# M4_Shield_Solar_Litio_V1_0.net
KiCad netlist of a schematic drawn in EAGLE
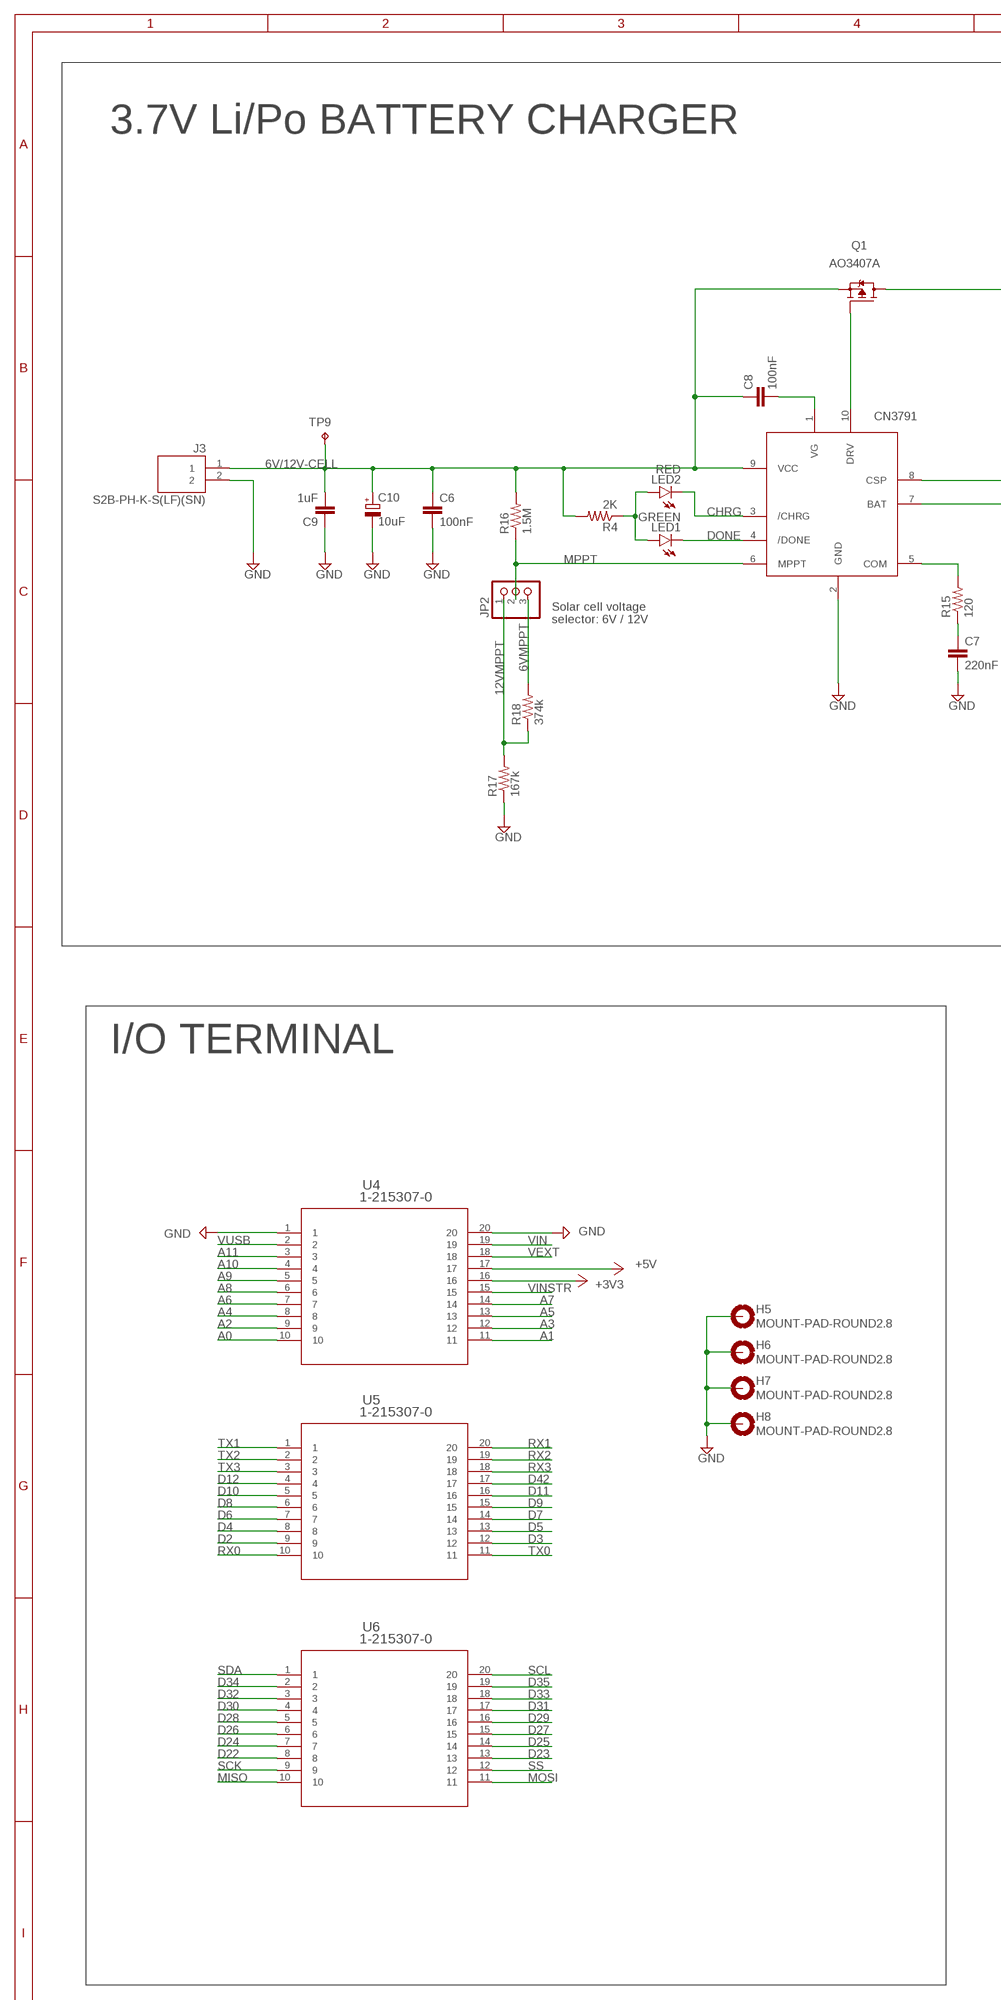
[diagram p0: schematic, sheet 1, part 1 of 2]
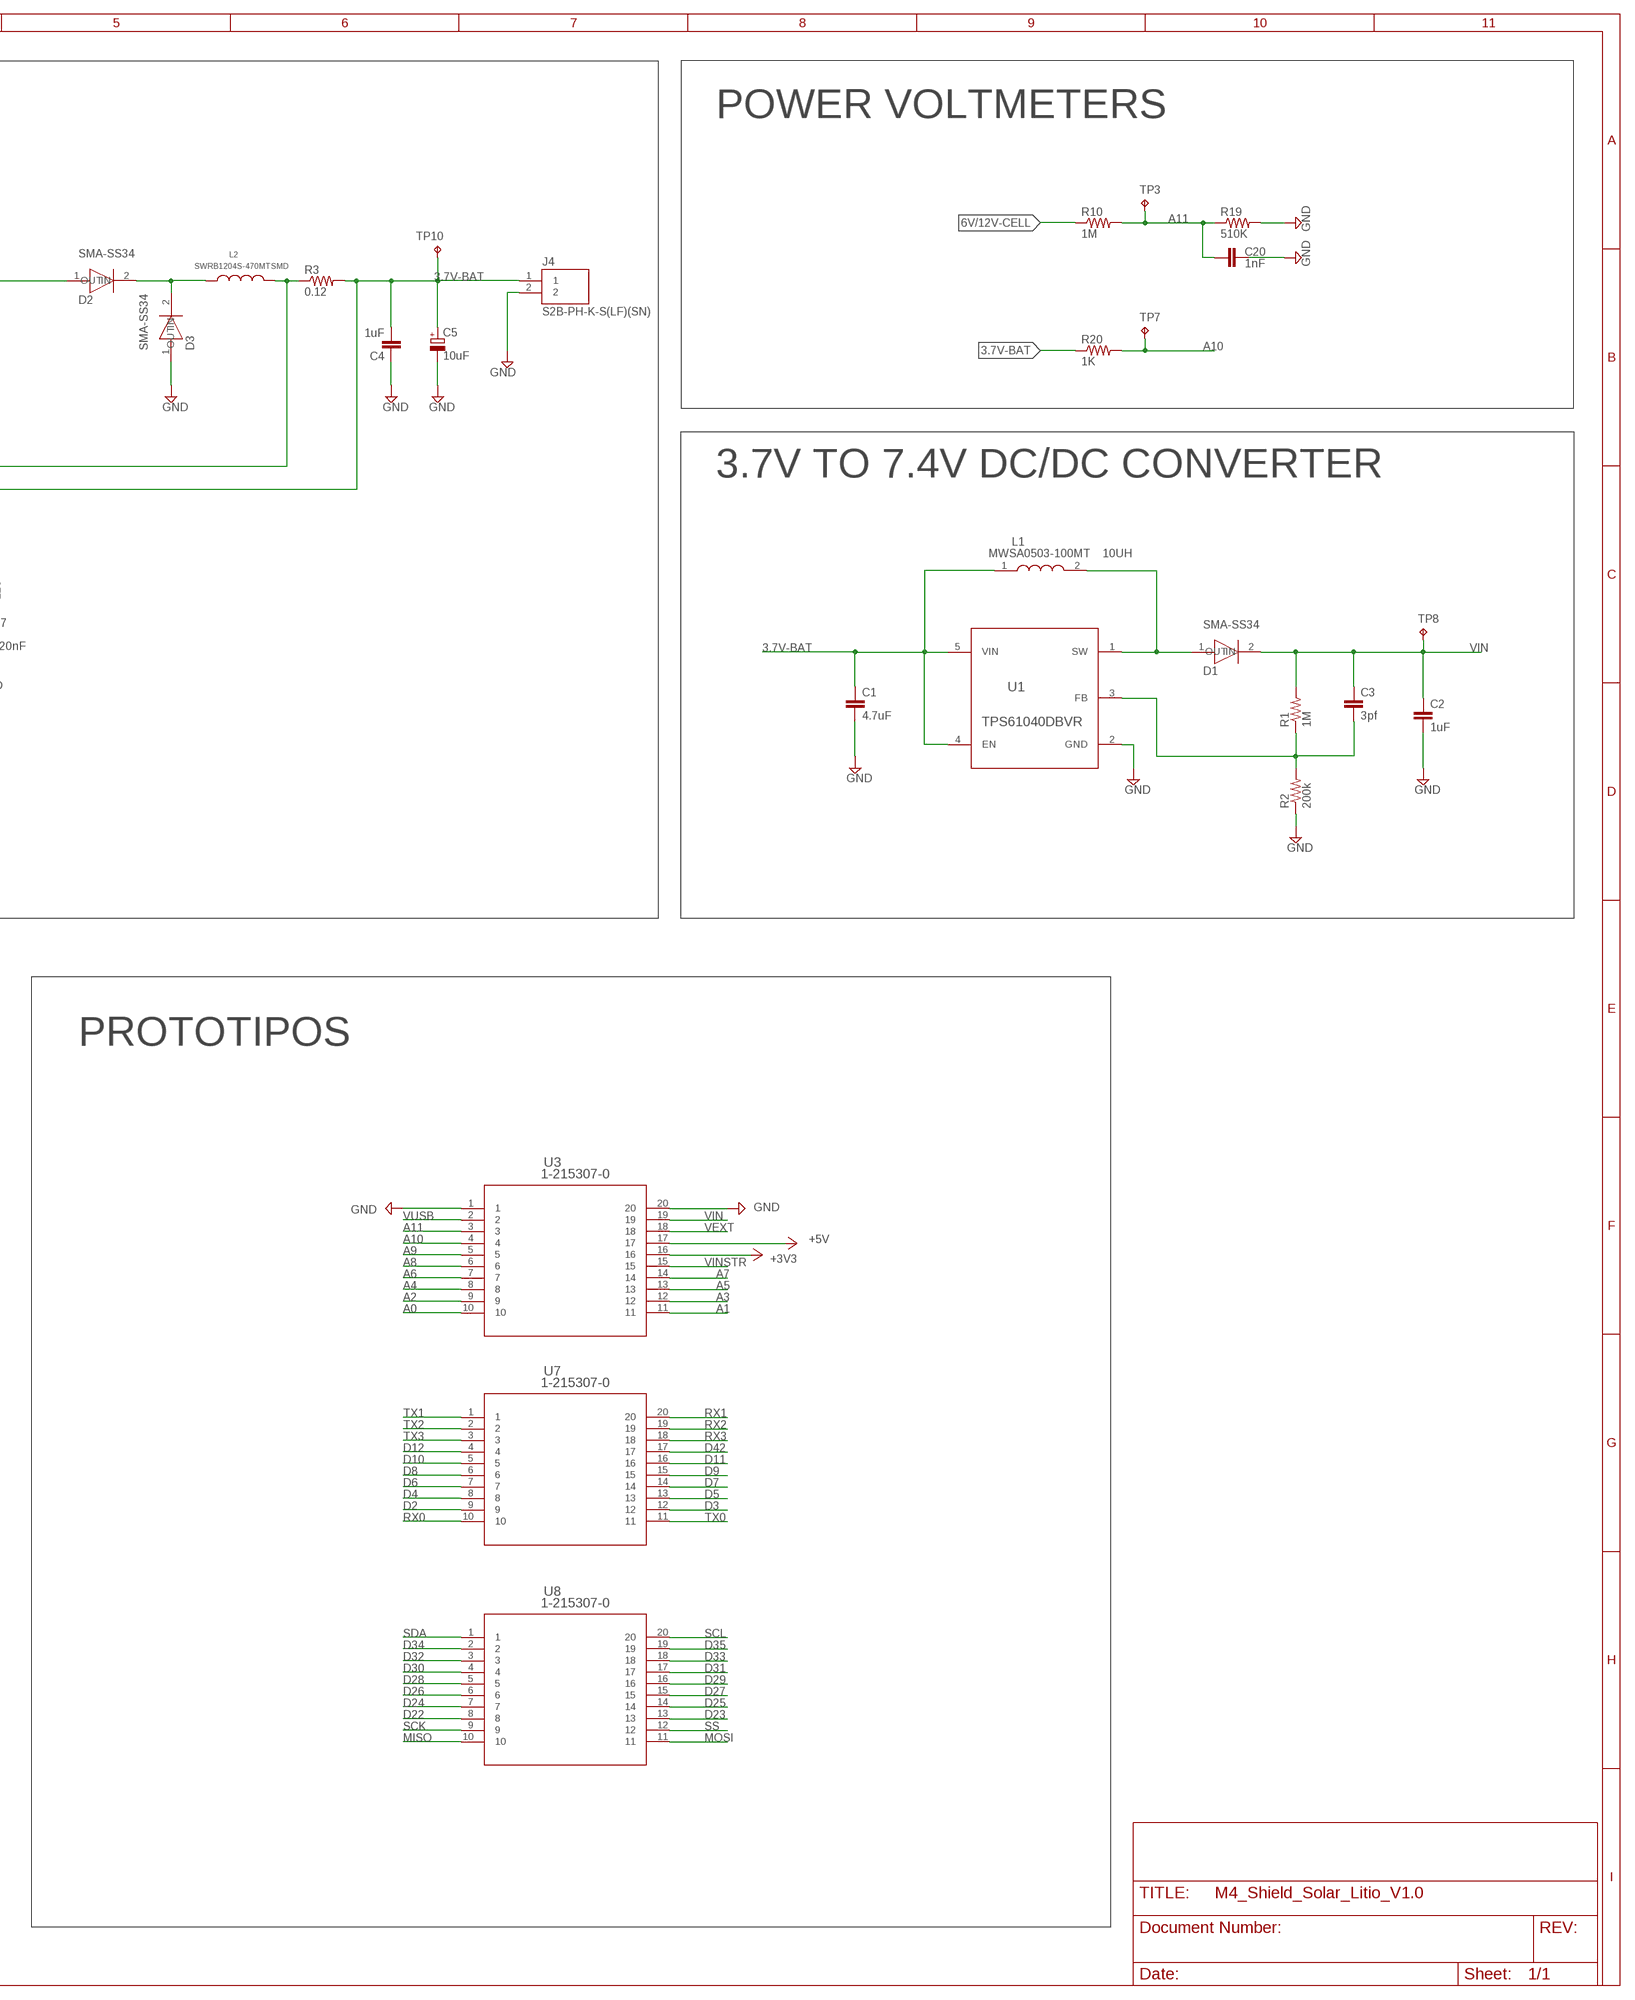
[diagram p1: schematic, sheet 1, part 2 of 2]

(export (version "E")
  (design (tool "Eeschema 10.0.6"))
  (components
    (comp (ref "C1")
      (value "4.7uF")
      (footprint "eagle-import:C0603K")
      (libsource (lib "eagle-import") (part "C-EUC0603K"))
    )
    (comp (ref "C2")
      (value "1uF")
      (footprint "eagle-import:C0603K")
      (libsource (lib "eagle-import") (part "C-EUC0603K"))
    )
    (comp (ref "C3")
      (value "3pf")
      (footprint "eagle-import:C0603K")
      (libsource (lib "eagle-import") (part "C-EUC0603K"))
    )
    (comp (ref "C4")
      (value "1uF")
      (footprint "eagle-import:C0603K")
      (libsource (lib "eagle-import") (part "C-EUC0603K"))
    )
    (comp (ref "C5")
      (value "10uF")
      (footprint "eagle-import:153CLV-0505")
      (libsource (lib "eagle-import") (part "CPOL-EU153CLV-0505"))
    )
    (comp (ref "C6")
      (value "100nF")
      (footprint "eagle-import:C0603K")
      (libsource (lib "eagle-import") (part "C-EUC0603K"))
    )
    (comp (ref "C7")
      (value "220nF")
      (footprint "eagle-import:C0603K")
      (libsource (lib "eagle-import") (part "C-EUC0603K"))
    )
    (comp (ref "C8")
      (value "100nF")
      (footprint "eagle-import:C0603K")
      (libsource (lib "eagle-import") (part "C-EUC0603K"))
    )
    (comp (ref "C9")
      (value "1uF")
      (footprint "eagle-import:C0603K")
      (libsource (lib "eagle-import") (part "C-EUC0603K"))
    )
    (comp (ref "C10")
      (value "10uF")
      (footprint "eagle-import:153CLV-0505")
      (libsource (lib "eagle-import") (part "CPOL-EU153CLV-0505"))
    )
    (comp (ref "C20")
      (value "1nF")
      (footprint "eagle-import:C0603K")
      (libsource (lib "eagle-import") (part "C-EUC0603K"))
    )
    (comp (ref "D1")
      (value "SMA-SS34")
      (footprint "eagle-import:SMA-SS34")
      (libsource (lib "eagle-import") (part "SMA-SS34"))
    )
    (comp (ref "D2")
      (value "SMA-SS34")
      (footprint "eagle-import:SMA-SS34")
      (libsource (lib "eagle-import") (part "SMA-SS34"))
    )
    (comp (ref "D3")
      (value "SMA-SS34")
      (footprint "eagle-import:SMA-SS34")
      (libsource (lib "eagle-import") (part "SMA-SS34"))
    )
    (comp (ref "H5")
      (value "MOUNT-PAD-ROUND2.8")
      (footprint "eagle-import:2,8-PAD")
      (libsource (lib "eagle-import") (part "MOUNT-PAD-ROUND2.8"))
    )
    (comp (ref "H6")
      (value "MOUNT-PAD-ROUND2.8")
      (footprint "eagle-import:2,8-PAD")
      (libsource (lib "eagle-import") (part "MOUNT-PAD-ROUND2.8"))
    )
    (comp (ref "H7")
      (value "MOUNT-PAD-ROUND2.8")
      (footprint "eagle-import:2,8-PAD")
      (libsource (lib "eagle-import") (part "MOUNT-PAD-ROUND2.8"))
    )
    (comp (ref "H8")
      (value "MOUNT-PAD-ROUND2.8")
      (footprint "eagle-import:2,8-PAD")
      (libsource (lib "eagle-import") (part "MOUNT-PAD-ROUND2.8"))
    )
    (comp (ref "J3")
      (value "S2B-PH-K-S(LF)(SN)")
      (footprint "eagle-import:JST_S2B-PH-K-S(LF)(SN)")
      (fields
        (field (name "DIGI-KEY_PART_NUMBER") "455-1719-ND")
        (field (name "MF") "JST Sales America Inc.")
        (field (name "MP") "S2B-PH-K-S_LF__SN_")
      )
      (libsource (lib "eagle-import") (part "S2B-PH-K-S(LF)(SN)"))
    )
    (comp (ref "J4")
      (value "S2B-PH-K-S(LF)(SN)")
      (footprint "eagle-import:JST_S2B-PH-K-S(LF)(SN)")
      (fields
        (field (name "DIGI-KEY_PART_NUMBER") "455-1719-ND")
        (field (name "MF") "JST Sales America Inc.")
        (field (name "MP") "S2B-PH-K-S_LF__SN_")
      )
      (libsource (lib "eagle-import") (part "S2B-PH-K-S(LF)(SN)"))
    )
    (comp (ref "JP2")
      (value "PINHD-1X3/90")
      (footprint "eagle-import:1X03_90")
      (libsource (lib "eagle-import") (part "PINHD-1X3/90"))
    )
    (comp (ref "L1")
      (value "MWSA0503-100MT 10UH")
      (footprint "eagle-import:MWSA0503")
      (fields (field (name "MANUFACTURER_PART_NUMBER") "MWSA0503"))
      (libsource (lib "eagle-import") (part "MWSA0503"))
    )
    (comp (ref "L2")
      (value "SWRB1204S-470MTSMD")
      (footprint "eagle-import:SWRB1204S-470MT")
      (libsource (lib "eagle-import") (part "SWRB1204S-470MTSMD"))
    )
    (comp (ref "LED1")
      (value "GREEN")
      (footprint "eagle-import:CHIPLED_0603")
      (libsource (lib "eagle-import") (part "LEDCHIPLED_0603"))
    )
    (comp (ref "LED2")
      (value "RED")
      (footprint "eagle-import:CHIPLED_0603")
      (libsource (lib "eagle-import") (part "LEDCHIPLED_0603"))
    )
    (comp (ref "Q1")
      (value "AO3407A")
      (footprint "eagle-import:SOT95P280X125-3N")
      (fields (field (name "DIGI-KEY_PART_NUMBER") "785-1006-1-ND") (field (name "MF") "Alpha &"))
      (libsource (lib "eagle-import") (part "AO3407A"))
    )
    (comp (ref "R1")
      (value "1M")
      (footprint "eagle-import:R0603")
      (libsource (lib "eagle-import") (part "R-US_R0603"))
    )
    (comp (ref "R2")
      (value "200k")
      (footprint "eagle-import:R0603")
      (libsource (lib "eagle-import") (part "R-US_R0603"))
    )
    (comp (ref "R3")
      (value "0.12")
      (footprint "eagle-import:R0805")
      (libsource (lib "eagle-import") (part "R-US_R0805"))
    )
    (comp (ref "R4")
      (value "2K")
      (footprint "eagle-import:R0603")
      (libsource (lib "eagle-import") (part "R-US_R0603"))
    )
    (comp (ref "R10")
      (value "1M")
      (footprint "eagle-import:R0603")
      (libsource (lib "eagle-import") (part "R-US_R0603"))
    )
    (comp (ref "R15")
      (value "120")
      (footprint "eagle-import:R0603")
      (libsource (lib "eagle-import") (part "R-US_R0603"))
    )
    (comp (ref "R16")
      (value "1.5M")
      (footprint "eagle-import:R0603")
      (libsource (lib "eagle-import") (part "R-US_R0603"))
    )
    (comp (ref "R17")
      (value "167k")
      (footprint "eagle-import:R0603")
      (libsource (lib "eagle-import") (part "R-US_R0603"))
    )
    (comp (ref "R18")
      (value "374k")
      (footprint "eagle-import:R0603")
      (libsource (lib "eagle-import") (part "R-US_R0603"))
    )
    (comp (ref "R19")
      (value "510K")
      (footprint "eagle-import:R0603")
      (libsource (lib "eagle-import") (part "R-US_R0603"))
    )
    (comp (ref "R20")
      (value "1K")
      (footprint "eagle-import:R0603")
      (libsource (lib "eagle-import") (part "R-US_R0603"))
    )
    (comp (ref "TP3")
      (value "TPB1,27")
      (footprint "eagle-import:B1,27")
      (libsource (lib "eagle-import") (part "TPB1,27"))
    )
    (comp (ref "TP7")
      (value "TPB1,27")
      (footprint "eagle-import:B1,27")
      (libsource (lib "eagle-import") (part "TPB1,27"))
    )
    (comp (ref "TP8")
      (value "TPB1,27")
      (footprint "eagle-import:B1,27")
      (libsource (lib "eagle-import") (part "TPB1,27"))
    )
    (comp (ref "TP9")
      (value "TPB1,27")
      (footprint "eagle-import:B1,27")
      (libsource (lib "eagle-import") (part "TPB1,27"))
    )
    (comp (ref "TP10")
      (value "TPB1,27")
      (footprint "eagle-import:B1,27")
      (libsource (lib "eagle-import") (part "TPB1,27"))
    )
    (comp (ref "U1")
      (value "TPS61040DBVR")
      (footprint "eagle-import:DBV0005A")
      (fields (field (name "MANUFACTURER") "Texas Instruments"))
      (libsource (lib "eagle-import") (part "TPS61040DBVR"))
    )
    (comp (ref "U2")
      (value "CN3791")
      (footprint "eagle-import:CN3791")
      (libsource (lib "eagle-import") (part "CN3791"))
    )
    (comp (ref "U3")
      (value "1-215307-0")
      (footprint "eagle-import:1-215307-0")
      (libsource (lib "eagle-import") (part "1-215307-0"))
    )
    (comp (ref "U4")
      (value "1-215307-0")
      (footprint "eagle-import:1-215307-0")
      (libsource (lib "eagle-import") (part "1-215307-0"))
    )
    (comp (ref "U5")
      (value "1-215307-0")
      (footprint "eagle-import:1-215307-0")
      (libsource (lib "eagle-import") (part "1-215307-0"))
    )
    (comp (ref "U6")
      (value "1-215307-0")
      (footprint "eagle-import:1-215307-0")
      (libsource (lib "eagle-import") (part "1-215307-0"))
    )
    (comp (ref "U7")
      (value "1-215307-0")
      (footprint "eagle-import:1-215307-0")
      (libsource (lib "eagle-import") (part "1-215307-0"))
    )
    (comp (ref "U8")
      (value "1-215307-0")
      (footprint "eagle-import:1-215307-0")
      (libsource (lib "eagle-import") (part "1-215307-0"))
    )
  )
  (nets
    (net (code "1") (name "+3V3") (class "Default")
      (node (ref "U3") (pin "16") (pinfunction "16_16") (pintype "passive"))
      (node (ref "U4") (pin "16") (pinfunction "16_16") (pintype "passive"))
    )
    (net (code "2") (name "+5V") (class "Default")
      (node (ref "U3") (pin "17") (pinfunction "17_17") (pintype "passive"))
      (node (ref "U4") (pin "17") (pinfunction "17_17") (pintype "passive"))
    )
    (net (code "3") (name "/6VMPPT") (class "Default")
      (node (ref "JP2") (pin "3") (pinfunction "3_3") (pintype "passive"))
      (node (ref "R18") (pin "2") (pinfunction "2_2") (pintype "passive"))
    )
    (net (code "4") (name "/12VMPPT") (class "Default")
      (node (ref "JP2") (pin "1") (pinfunction "1_1") (pintype "passive"))
      (node (ref "R17") (pin "2") (pinfunction "2_2") (pintype "passive"))
      (node (ref "R18") (pin "1") (pinfunction "1_1") (pintype "passive"))
    )
    (net (code "5") (name "/A0") (class "Default")
      (node (ref "U3") (pin "10") (pinfunction "10_10") (pintype "passive"))
      (node (ref "U4") (pin "10") (pinfunction "10_10") (pintype "passive"))
    )
    (net (code "6") (name "/A1") (class "Default")
      (node (ref "U3") (pin "11") (pinfunction "11_11") (pintype "passive"))
      (node (ref "U4") (pin "11") (pinfunction "11_11") (pintype "passive"))
    )
    (net (code "7") (name "/A2") (class "Default")
      (node (ref "U3") (pin "9") (pinfunction "9_9") (pintype "passive"))
      (node (ref "U4") (pin "9") (pinfunction "9_9") (pintype "passive"))
    )
    (net (code "8") (name "/A3") (class "Default")
      (node (ref "U3") (pin "12") (pinfunction "12_12") (pintype "passive"))
      (node (ref "U4") (pin "12") (pinfunction "12_12") (pintype "passive"))
    )
    (net (code "9") (name "/A4") (class "Default")
      (node (ref "U3") (pin "8") (pinfunction "8_8") (pintype "passive"))
      (node (ref "U4") (pin "8") (pinfunction "8_8") (pintype "passive"))
    )
    (net (code "10") (name "/A5") (class "Default")
      (node (ref "U3") (pin "13") (pinfunction "13_13") (pintype "passive"))
      (node (ref "U4") (pin "13") (pinfunction "13_13") (pintype "passive"))
    )
    (net (code "11") (name "/A6") (class "Default")
      (node (ref "U3") (pin "7") (pinfunction "7_7") (pintype "passive"))
      (node (ref "U4") (pin "7") (pinfunction "7_7") (pintype "passive"))
    )
    (net (code "12") (name "/A7") (class "Default")
      (node (ref "U3") (pin "14") (pinfunction "14_14") (pintype "passive"))
      (node (ref "U4") (pin "14") (pinfunction "14_14") (pintype "passive"))
    )
    (net (code "13") (name "/A8") (class "Default")
      (node (ref "U3") (pin "6") (pinfunction "6_6") (pintype "passive"))
      (node (ref "U4") (pin "6") (pinfunction "6_6") (pintype "passive"))
    )
    (net (code "14") (name "/A9") (class "Default")
      (node (ref "U3") (pin "5") (pinfunction "5_5") (pintype "passive"))
      (node (ref "U4") (pin "5") (pinfunction "5_5") (pintype "passive"))
    )
    (net (code "15") (name "/A10") (class "Default")
      (node (ref "R20") (pin "2") (pinfunction "2_2") (pintype "passive"))
      (node (ref "TP7") (pin "TP") (pinfunction "TP_TP") (pintype "input"))
      (node (ref "U3") (pin "4") (pinfunction "4_4") (pintype "passive"))
      (node (ref "U4") (pin "4") (pinfunction "4_4") (pintype "passive"))
    )
    (net (code "16") (name "/A11") (class "Default")
      (node (ref "C20") (pin "1") (pinfunction "1_1") (pintype "passive"))
      (node (ref "R10") (pin "2") (pinfunction "2_2") (pintype "passive"))
      (node (ref "R19") (pin "1") (pinfunction "1_1") (pintype "passive"))
      (node (ref "TP3") (pin "TP") (pinfunction "TP_TP") (pintype "input"))
      (node (ref "U3") (pin "3") (pinfunction "3_3") (pintype "passive"))
      (node (ref "U4") (pin "3") (pinfunction "3_3") (pintype "passive"))
    )
    (net (code "17") (name "/CHRG") (class "Default")
      (node (ref "LED2") (pin "C") (pinfunction "C_C") (pintype "passive"))
      (node (ref "U2") (pin "3") (pinfunction "/CHRG_3") (pintype "bidirectional"))
    )
    (net (code "18") (name "/D2") (class "Default")
      (node (ref "U5") (pin "9") (pinfunction "9_9") (pintype "passive"))
      (node (ref "U7") (pin "9") (pinfunction "9_9") (pintype "passive"))
    )
    (net (code "19") (name "/D3") (class "Default")
      (node (ref "U5") (pin "12") (pinfunction "12_12") (pintype "passive"))
      (node (ref "U7") (pin "12") (pinfunction "12_12") (pintype "passive"))
    )
    (net (code "20") (name "/D4") (class "Default")
      (node (ref "U5") (pin "8") (pinfunction "8_8") (pintype "passive"))
      (node (ref "U7") (pin "8") (pinfunction "8_8") (pintype "passive"))
    )
    (net (code "21") (name "/D5") (class "Default")
      (node (ref "U5") (pin "13") (pinfunction "13_13") (pintype "passive"))
      (node (ref "U7") (pin "13") (pinfunction "13_13") (pintype "passive"))
    )
    (net (code "22") (name "/D6") (class "Default")
      (node (ref "U5") (pin "7") (pinfunction "7_7") (pintype "passive"))
      (node (ref "U7") (pin "7") (pinfunction "7_7") (pintype "passive"))
    )
    (net (code "23") (name "/D7") (class "Default")
      (node (ref "U5") (pin "14") (pinfunction "14_14") (pintype "passive"))
      (node (ref "U7") (pin "14") (pinfunction "14_14") (pintype "passive"))
    )
    (net (code "24") (name "/D8") (class "Default")
      (node (ref "U5") (pin "6") (pinfunction "6_6") (pintype "passive"))
      (node (ref "U7") (pin "6") (pinfunction "6_6") (pintype "passive"))
    )
    (net (code "25") (name "/D9") (class "Default")
      (node (ref "U5") (pin "15") (pinfunction "15_15") (pintype "passive"))
      (node (ref "U7") (pin "15") (pinfunction "15_15") (pintype "passive"))
    )
    (net (code "26") (name "/D10") (class "Default")
      (node (ref "U5") (pin "5") (pinfunction "5_5") (pintype "passive"))
      (node (ref "U7") (pin "5") (pinfunction "5_5") (pintype "passive"))
    )
    (net (code "27") (name "/D11") (class "Default")
      (node (ref "U5") (pin "16") (pinfunction "16_16") (pintype "passive"))
      (node (ref "U7") (pin "16") (pinfunction "16_16") (pintype "passive"))
    )
    (net (code "28") (name "/D12") (class "Default")
      (node (ref "U5") (pin "4") (pinfunction "4_4") (pintype "passive"))
      (node (ref "U7") (pin "4") (pinfunction "4_4") (pintype "passive"))
    )
    (net (code "29") (name "/D22") (class "Default")
      (node (ref "U6") (pin "8") (pinfunction "8_8") (pintype "passive"))
      (node (ref "U8") (pin "8") (pinfunction "8_8") (pintype "passive"))
    )
    (net (code "30") (name "/D23") (class "Default")
      (node (ref "U6") (pin "13") (pinfunction "13_13") (pintype "passive"))
      (node (ref "U8") (pin "13") (pinfunction "13_13") (pintype "passive"))
    )
    (net (code "31") (name "/D24") (class "Default")
      (node (ref "U6") (pin "7") (pinfunction "7_7") (pintype "passive"))
      (node (ref "U8") (pin "7") (pinfunction "7_7") (pintype "passive"))
    )
    (net (code "32") (name "/D25") (class "Default")
      (node (ref "U6") (pin "14") (pinfunction "14_14") (pintype "passive"))
      (node (ref "U8") (pin "14") (pinfunction "14_14") (pintype "passive"))
    )
    (net (code "33") (name "/D26") (class "Default")
      (node (ref "U6") (pin "6") (pinfunction "6_6") (pintype "passive"))
      (node (ref "U8") (pin "6") (pinfunction "6_6") (pintype "passive"))
    )
    (net (code "34") (name "/D27") (class "Default")
      (node (ref "U6") (pin "15") (pinfunction "15_15") (pintype "passive"))
      (node (ref "U8") (pin "15") (pinfunction "15_15") (pintype "passive"))
    )
    (net (code "35") (name "/D28") (class "Default")
      (node (ref "U6") (pin "5") (pinfunction "5_5") (pintype "passive"))
      (node (ref "U8") (pin "5") (pinfunction "5_5") (pintype "passive"))
    )
    (net (code "36") (name "/D29") (class "Default")
      (node (ref "U6") (pin "16") (pinfunction "16_16") (pintype "passive"))
      (node (ref "U8") (pin "16") (pinfunction "16_16") (pintype "passive"))
    )
    (net (code "37") (name "/D30") (class "Default")
      (node (ref "U6") (pin "4") (pinfunction "4_4") (pintype "passive"))
      (node (ref "U8") (pin "4") (pinfunction "4_4") (pintype "passive"))
    )
    (net (code "38") (name "/D31") (class "Default")
      (node (ref "U6") (pin "17") (pinfunction "17_17") (pintype "passive"))
      (node (ref "U8") (pin "17") (pinfunction "17_17") (pintype "passive"))
    )
    (net (code "39") (name "/D32") (class "Default")
      (node (ref "U6") (pin "3") (pinfunction "3_3") (pintype "passive"))
      (node (ref "U8") (pin "3") (pinfunction "3_3") (pintype "passive"))
    )
    (net (code "40") (name "/D33") (class "Default")
      (node (ref "U6") (pin "18") (pinfunction "18_18") (pintype "passive"))
      (node (ref "U8") (pin "18") (pinfunction "18_18") (pintype "passive"))
    )
    (net (code "41") (name "/D34") (class "Default")
      (node (ref "U6") (pin "2") (pinfunction "2_2") (pintype "passive"))
      (node (ref "U8") (pin "2") (pinfunction "2_2") (pintype "passive"))
    )
    (net (code "42") (name "/D35") (class "Default")
      (node (ref "U6") (pin "19") (pinfunction "19_19") (pintype "passive"))
      (node (ref "U8") (pin "19") (pinfunction "19_19") (pintype "passive"))
    )
    (net (code "43") (name "/D42") (class "Default")
      (node (ref "U5") (pin "17") (pinfunction "17_17") (pintype "passive"))
      (node (ref "U7") (pin "17") (pinfunction "17_17") (pintype "passive"))
    )
    (net (code "44") (name "/DONE") (class "Default")
      (node (ref "LED1") (pin "C") (pinfunction "C_C") (pintype "passive"))
      (node (ref "U2") (pin "4") (pinfunction "/DONE_4") (pintype "bidirectional"))
    )
    (net (code "45") (name "/MISO") (class "Default")
      (node (ref "U6") (pin "10") (pinfunction "10_10") (pintype "passive"))
      (node (ref "U8") (pin "10") (pinfunction "10_10") (pintype "passive"))
    )
    (net (code "46") (name "/MOSI") (class "Default")
      (node (ref "U6") (pin "11") (pinfunction "11_11") (pintype "passive"))
      (node (ref "U8") (pin "11") (pinfunction "11_11") (pintype "passive"))
    )
    (net (code "47") (name "/MPPT") (class "Default")
      (node (ref "JP2") (pin "2") (pinfunction "2_2") (pintype "passive"))
      (node (ref "R16") (pin "1") (pinfunction "1_1") (pintype "passive"))
      (node (ref "U2") (pin "6") (pinfunction "MPPT_6") (pintype "bidirectional"))
    )
    (net (code "48") (name "/RX0") (class "Default")
      (node (ref "U5") (pin "10") (pinfunction "10_10") (pintype "passive"))
      (node (ref "U7") (pin "10") (pinfunction "10_10") (pintype "passive"))
    )
    (net (code "49") (name "/RX1") (class "Default")
      (node (ref "U5") (pin "20") (pinfunction "20_20") (pintype "passive"))
      (node (ref "U7") (pin "20") (pinfunction "20_20") (pintype "passive"))
    )
    (net (code "50") (name "/RX2") (class "Default")
      (node (ref "U5") (pin "19") (pinfunction "19_19") (pintype "passive"))
      (node (ref "U7") (pin "19") (pinfunction "19_19") (pintype "passive"))
    )
    (net (code "51") (name "/RX3") (class "Default")
      (node (ref "U5") (pin "18") (pinfunction "18_18") (pintype "passive"))
      (node (ref "U7") (pin "18") (pinfunction "18_18") (pintype "passive"))
    )
    (net (code "52") (name "/SCK") (class "Default")
      (node (ref "U6") (pin "9") (pinfunction "9_9") (pintype "passive"))
      (node (ref "U8") (pin "9") (pinfunction "9_9") (pintype "passive"))
    )
    (net (code "53") (name "/SCL") (class "Default")
      (node (ref "U6") (pin "20") (pinfunction "20_20") (pintype "passive"))
      (node (ref "U8") (pin "20") (pinfunction "20_20") (pintype "passive"))
    )
    (net (code "54") (name "/SDA") (class "Default")
      (node (ref "U6") (pin "1") (pinfunction "1_1") (pintype "passive"))
      (node (ref "U8") (pin "1") (pinfunction "1_1") (pintype "passive"))
    )
    (net (code "55") (name "/SS") (class "Default")
      (node (ref "U6") (pin "12") (pinfunction "12_12") (pintype "passive"))
      (node (ref "U8") (pin "12") (pinfunction "12_12") (pintype "passive"))
    )
    (net (code "56") (name "/TX0") (class "Default")
      (node (ref "U5") (pin "11") (pinfunction "11_11") (pintype "passive"))
      (node (ref "U7") (pin "11") (pinfunction "11_11") (pintype "passive"))
    )
    (net (code "57") (name "/TX1") (class "Default")
      (node (ref "U5") (pin "1") (pinfunction "1_1") (pintype "passive"))
      (node (ref "U7") (pin "1") (pinfunction "1_1") (pintype "passive"))
    )
    (net (code "58") (name "/TX2") (class "Default")
      (node (ref "U5") (pin "2") (pinfunction "2_2") (pintype "passive"))
      (node (ref "U7") (pin "2") (pinfunction "2_2") (pintype "passive"))
    )
    (net (code "59") (name "/TX3") (class "Default")
      (node (ref "U5") (pin "3") (pinfunction "3_3") (pintype "passive"))
      (node (ref "U7") (pin "3") (pinfunction "3_3") (pintype "passive"))
    )
    (net (code "60") (name "/VEXT") (class "Default")
      (node (ref "U3") (pin "18") (pinfunction "18_18") (pintype "passive"))
      (node (ref "U4") (pin "18") (pinfunction "18_18") (pintype "passive"))
    )
    (net (code "61") (name "/VIN") (class "Default")
      (node (ref "C2") (pin "1") (pinfunction "1_1") (pintype "passive"))
      (node (ref "C3") (pin "1") (pinfunction "1_1") (pintype "passive"))
      (node (ref "D1") (pin "2") (pinfunction "OUT_2") (pintype "bidirectional"))
      (node (ref "R1") (pin "2") (pinfunction "2_2") (pintype "passive"))
      (node (ref "TP8") (pin "TP") (pinfunction "TP_TP") (pintype "input"))
      (node (ref "U3") (pin "19") (pinfunction "19_19") (pintype "passive"))
      (node (ref "U4") (pin "19") (pinfunction "19_19") (pintype "passive"))
    )
    (net (code "62") (name "/VINSTR") (class "Default")
      (node (ref "U3") (pin "15") (pinfunction "15_15") (pintype "passive"))
      (node (ref "U4") (pin "15") (pinfunction "15_15") (pintype "passive"))
    )
    (net (code "63") (name "/VUSB") (class "Default")
      (node (ref "U3") (pin "2") (pinfunction "2_2") (pintype "passive"))
      (node (ref "U4") (pin "2") (pinfunction "2_2") (pintype "passive"))
    )
    (net (code "64") (name "3.7V-BAT") (class "Default")
      (node (ref "C1") (pin "1") (pinfunction "1_1") (pintype "passive"))
      (node (ref "C4") (pin "2") (pinfunction "2_2") (pintype "passive"))
      (node (ref "C5") (pin "+") (pinfunction "+_+") (pintype "passive"))
      (node (ref "J4") (pin "1") (pinfunction "1_1") (pintype "passive"))
      (node (ref "L1") (pin "1") (pinfunction "1_1") (pintype "bidirectional"))
      (node (ref "R20") (pin "1") (pinfunction "1_1") (pintype "passive"))
      (node (ref "R3") (pin "2") (pinfunction "2_2") (pintype "passive"))
      (node (ref "TP10") (pin "TP") (pinfunction "TP_TP") (pintype "input"))
      (node (ref "U1") (pin "4") (pinfunction "EN_4") (pintype "input"))
      (node (ref "U1") (pin "5") (pinfunction "VIN_5") (pintype "power_in"))
      (node (ref "U2") (pin "7") (pinfunction "BAT_7") (pintype "bidirectional"))
    )
    (net (code "65") (name "6V{slash}12V-CELL") (class "Default")
      (node (ref "C10") (pin "+") (pinfunction "+_+") (pintype "passive"))
      (node (ref "C6") (pin "1") (pinfunction "1_1") (pintype "passive"))
      (node (ref "C8") (pin "1") (pinfunction "1_1") (pintype "passive"))
      (node (ref "C9") (pin "2") (pinfunction "2_2") (pintype "passive"))
      (node (ref "J3") (pin "1") (pinfunction "1_1") (pintype "passive"))
      (node (ref "Q1") (pin "2") (pinfunction "S_2") (pintype "passive"))
      (node (ref "R10") (pin "1") (pinfunction "1_1") (pintype "passive"))
      (node (ref "R16") (pin "2") (pinfunction "2_2") (pintype "passive"))
      (node (ref "R4") (pin "2") (pinfunction "2_2") (pintype "passive"))
      (node (ref "TP9") (pin "TP") (pinfunction "TP_TP") (pintype "input"))
      (node (ref "U2") (pin "9") (pinfunction "VCC_9") (pintype "bidirectional"))
    )
    (net (code "66") (name "GND") (class "Default")
      (node (ref "C1") (pin "2") (pinfunction "2_2") (pintype "passive"))
      (node (ref "C10") (pin "-") (pinfunction "-_-") (pintype "passive"))
      (node (ref "C2") (pin "2") (pinfunction "2_2") (pintype "passive"))
      (node (ref "C20") (pin "2") (pinfunction "2_2") (pintype "passive"))
      (node (ref "C4") (pin "1") (pinfunction "1_1") (pintype "passive"))
      (node (ref "C5") (pin "-") (pinfunction "-_-") (pintype "passive"))
      (node (ref "C6") (pin "2") (pinfunction "2_2") (pintype "passive"))
      (node (ref "C7") (pin "2") (pinfunction "2_2") (pintype "passive"))
      (node (ref "C9") (pin "1") (pinfunction "1_1") (pintype "passive"))
      (node (ref "D3") (pin "1") (pinfunction "IN_1") (pintype "input"))
      (node (ref "H5") (pin "B2,8") (pinfunction "MOUNT_B2,8") (pintype "passive"))
      (node (ref "H6") (pin "B2,8") (pinfunction "MOUNT_B2,8") (pintype "passive"))
      (node (ref "H7") (pin "B2,8") (pinfunction "MOUNT_B2,8") (pintype "passive"))
      (node (ref "H8") (pin "B2,8") (pinfunction "MOUNT_B2,8") (pintype "passive"))
      (node (ref "J3") (pin "2") (pinfunction "2_2") (pintype "passive"))
      (node (ref "J4") (pin "2") (pinfunction "2_2") (pintype "passive"))
      (node (ref "R17") (pin "1") (pinfunction "1_1") (pintype "passive"))
      (node (ref "R19") (pin "2") (pinfunction "2_2") (pintype "passive"))
      (node (ref "R2") (pin "1") (pinfunction "1_1") (pintype "passive"))
      (node (ref "U1") (pin "2") (pinfunction "GND_2") (pintype "power_in"))
      (node (ref "U2") (pin "2") (pinfunction "GND_2") (pintype "bidirectional"))
      (node (ref "U3") (pin "1") (pinfunction "1_1") (pintype "passive"))
      (node (ref "U3") (pin "20") (pinfunction "20_20") (pintype "passive"))
      (node (ref "U4") (pin "1") (pinfunction "1_1") (pintype "passive"))
      (node (ref "U4") (pin "20") (pinfunction "20_20") (pintype "passive"))
    )
    (net (code "67") (name "Net-(C7-Pad1)") (class "Default")
      (node (ref "C7") (pin "1") (pinfunction "1_1") (pintype "passive"))
      (node (ref "R15") (pin "1") (pinfunction "1_1") (pintype "passive"))
    )
    (net (code "68") (name "Net-(D1-IN)") (class "Default")
      (node (ref "D1") (pin "1") (pinfunction "IN_1") (pintype "input"))
      (node (ref "L1") (pin "2") (pinfunction "2_2") (pintype "bidirectional"))
      (node (ref "U1") (pin "1") (pinfunction "SW_1") (pintype "power_in"))
    )
    (net (code "69") (name "Net-(D2-IN)") (class "Default")
      (node (ref "D2") (pin "1") (pinfunction "IN_1") (pintype "input"))
      (node (ref "Q1") (pin "3") (pinfunction "D_3") (pintype "passive"))
    )
    (net (code "70") (name "Net-(D2-OUT)") (class "Default")
      (node (ref "D2") (pin "2") (pinfunction "OUT_2") (pintype "bidirectional"))
      (node (ref "D3") (pin "2") (pinfunction "OUT_2") (pintype "bidirectional"))
      (node (ref "L2") (pin "1") (pinfunction "P$1_1") (pintype "bidirectional"))
    )
    (net (code "71") (name "Net-(L2-P$2)") (class "Default")
      (node (ref "L2") (pin "2") (pinfunction "P$2_2") (pintype "bidirectional"))
      (node (ref "R3") (pin "1") (pinfunction "1_1") (pintype "passive"))
      (node (ref "U2") (pin "8") (pinfunction "CSP_8") (pintype "bidirectional"))
    )
    (net (code "72") (name "Net-(LED1-PadA)") (class "Default")
      (node (ref "LED1") (pin "A") (pinfunction "A_A") (pintype "passive"))
      (node (ref "LED2") (pin "A") (pinfunction "A_A") (pintype "passive"))
      (node (ref "R4") (pin "1") (pinfunction "1_1") (pintype "passive"))
    )
    (net (code "73") (name "Net-(Q1-G)") (class "Default")
      (node (ref "Q1") (pin "1") (pinfunction "G_1") (pintype "passive"))
      (node (ref "U2") (pin "10") (pinfunction "DRV_10") (pintype "bidirectional"))
    )
    (net (code "74") (name "Net-(U1-FB)") (class "Default")
      (node (ref "C3") (pin "2") (pinfunction "2_2") (pintype "passive"))
      (node (ref "R1") (pin "1") (pinfunction "1_1") (pintype "passive"))
      (node (ref "R2") (pin "2") (pinfunction "2_2") (pintype "passive"))
      (node (ref "U1") (pin "3") (pinfunction "FB_3") (pintype "input"))
    )
    (net (code "75") (name "Net-(U2-COM)") (class "Default")
      (node (ref "R15") (pin "2") (pinfunction "2_2") (pintype "passive"))
      (node (ref "U2") (pin "5") (pinfunction "COM_5") (pintype "bidirectional"))
    )
    (net (code "76") (name "Net-(U2-VG)") (class "Default")
      (node (ref "C8") (pin "2") (pinfunction "2_2") (pintype "passive"))
      (node (ref "U2") (pin "1") (pinfunction "VG_1") (pintype "bidirectional"))
    )
  )
)
